# base-board.net
KiCad netlist of a schematic drawn in Altium Designer
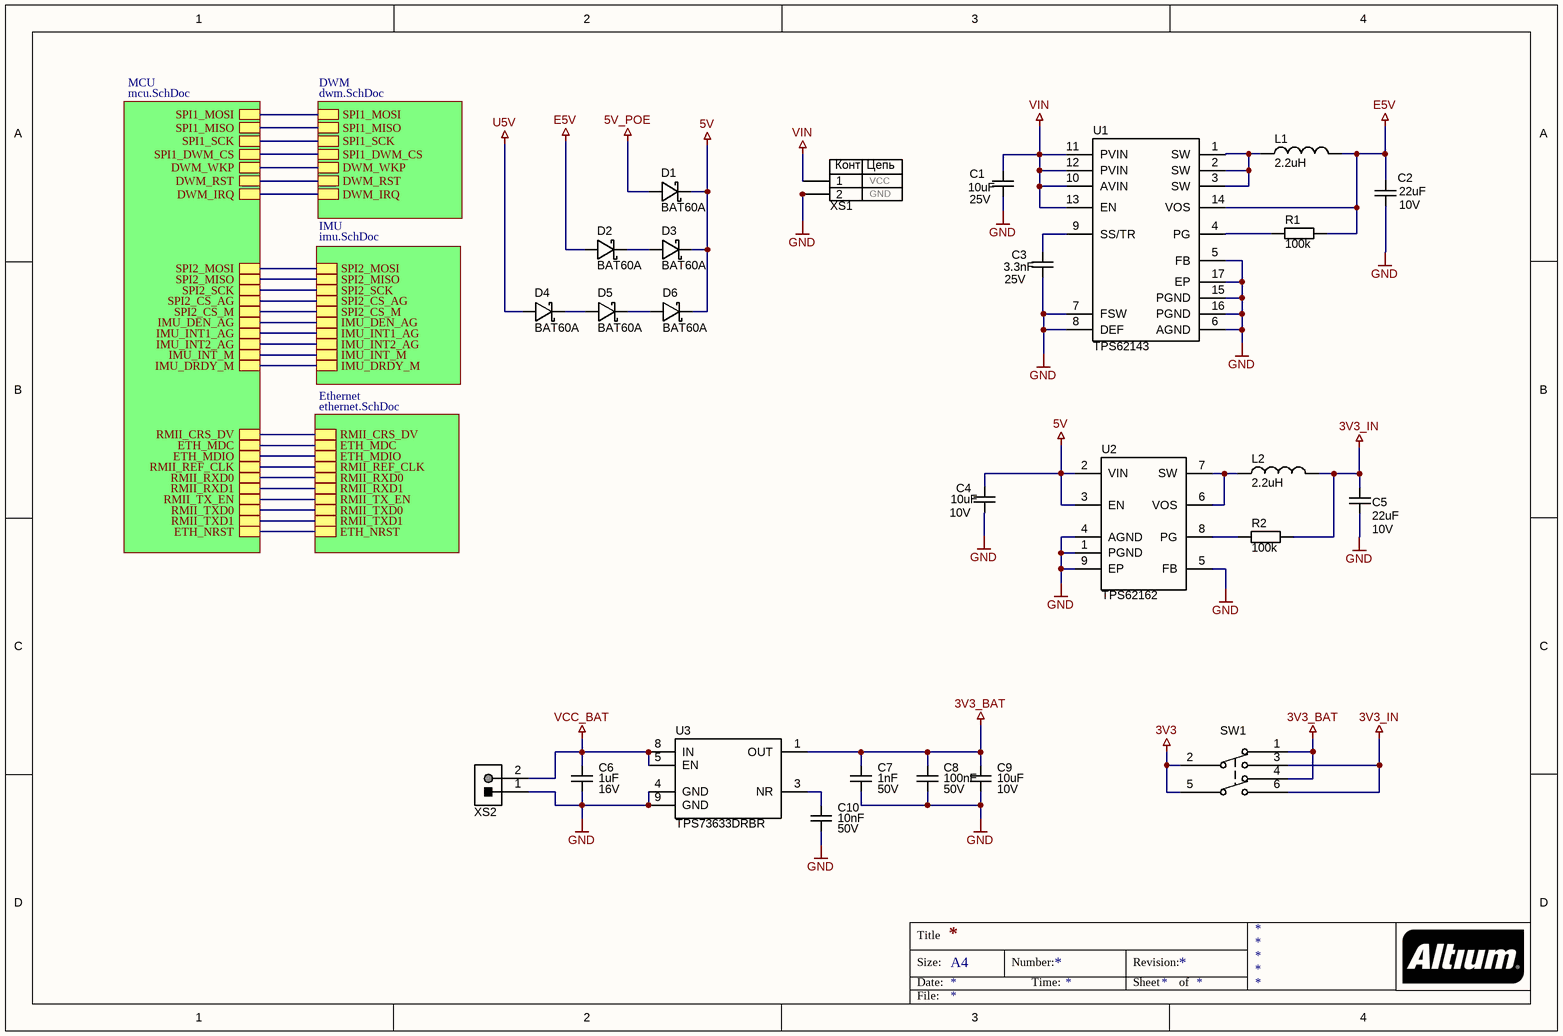
[diagram p0: base-board.SchDoc]

(export (version "E")
  (design (tool "Eeschema 10.0.6"))
  (components
    (comp (ref "C1")
      (value "10uF")
      (footprint "C1210")
      (fields (field (name "VOLTAGE") "25V") (field (name "Comment") "C1210"))
      (libsource (lib "DZ_LIB") (part "C1210"))
    )
    (comp (ref "C2")
      (value "22uF")
      (footprint "C1210")
      (fields (field (name "VOLTAGE") "10V") (field (name "Comment") "C1210"))
      (libsource (lib "DZ_LIB") (part "C1210"))
    )
    (comp (ref "C3")
      (value "3.3nF")
      (footprint "C0603")
      (fields (field (name "VOLTAGE") "25V") (field (name "Comment") "C0603"))
      (libsource (lib "DZ_LIB") (part "C0603"))
    )
    (comp (ref "C4")
      (value "10uF")
      (footprint "C0805")
      (fields (field (name "VOLTAGE") "10V") (field (name "Comment") "C0805"))
      (libsource (lib "DZ_LIB") (part "C0805"))
    )
    (comp (ref "C5")
      (value "22uF")
      (footprint "C0805")
      (fields (field (name "VOLTAGE") "10V") (field (name "Comment") "C0805"))
      (libsource (lib "DZ_LIB") (part "C0805"))
    )
    (comp (ref "C6")
      (value "1uF")
      (footprint "C0805")
      (fields (field (name "VOLTAGE") "16V") (field (name "Comment") "C0805"))
      (libsource (lib "DZ_LIB") (part "C0805"))
    )
    (comp (ref "C7")
      (value "1nF")
      (footprint "C0805")
      (fields (field (name "VOLTAGE") "50V") (field (name "Comment") "C0805"))
      (libsource (lib "DZ_LIB") (part "C0805"))
    )
    (comp (ref "C8")
      (value "100nF")
      (footprint "C0603")
      (fields (field (name "VOLTAGE") "50V") (field (name "Comment") "C0603"))
      (libsource (lib "DZ_LIB") (part "C0603"))
    )
    (comp (ref "C9")
      (value "10uF")
      (footprint "C0603")
      (fields (field (name "VOLTAGE") "10V") (field (name "Comment") "C0603"))
      (libsource (lib "DZ_LIB") (part "C0603"))
    )
    (comp (ref "C10")
      (value "10nF")
      (footprint "C0603")
      (fields (field (name "VOLTAGE") "50V") (field (name "Comment") "C0603"))
      (libsource (lib "DZ_LIB") (part "C0603"))
    )
    (comp (ref "D1")
      (value "BAT60A")
      (footprint "SOD-323-2")
      (description "Shottky Diode 10V 3A")
      (libsource (lib "DZ_LIB") (part "BAT60J"))
    )
    (comp (ref "D2")
      (value "BAT60A")
      (footprint "SOD-323-2")
      (description "Shottky Diode 10V 3A")
      (libsource (lib "DZ_LIB") (part "BAT60J"))
    )
    (comp (ref "D3")
      (value "BAT60A")
      (footprint "SOD-323-2")
      (description "Shottky Diode 10V 3A")
      (libsource (lib "DZ_LIB") (part "BAT60J"))
    )
    (comp (ref "D4")
      (value "BAT60A")
      (footprint "SOD-323-2")
      (description "Shottky Diode 10V 3A")
      (libsource (lib "DZ_LIB") (part "BAT60J"))
    )
    (comp (ref "D5")
      (value "BAT60A")
      (footprint "SOD-323-2")
      (description "Shottky Diode 10V 3A")
      (libsource (lib "DZ_LIB") (part "BAT60J"))
    )
    (comp (ref "D6")
      (value "BAT60A")
      (footprint "SOD-323-2")
      (description "Shottky Diode 10V 3A")
      (libsource (lib "DZ_LIB") (part "BAT60J"))
    )
    (comp (ref "L1")
      (value "2.2uH")
      (footprint "IND2220")
      (description "FIXED IND 2.2UH 2.5A 31 MOHM SMD")
      (fields (field (name "Comment") "LQH55PN2R2NR0"))
      (libsource (lib "DZ_LIB") (part "LQH55PN2R2NR0"))
    )
    (comp (ref "L2")
      (value "2.2uH")
      (footprint "IND2220")
      (description "FIXED IND 2.2UH 2.5A 31 MOHM SMD")
      (fields (field (name "Comment") "LQH55PN2R2NR0"))
      (libsource (lib "DZ_LIB") (part "LQH55PN2R2NR0"))
    )
    (comp (ref "R1")
      (value "100k")
      (footprint "SMD0603")
      (fields (field (name "Comment") "R0603"))
      (libsource (lib "DZ_LIB") (part "R0603"))
    )
    (comp (ref "R2")
      (value "100k")
      (footprint "SMD0603")
      (fields (field (name "Comment") "R0603"))
      (libsource (lib "DZ_LIB") (part "R0603"))
    )
    (comp (ref "SW1")
      (value "JS202011SCQN")
      (footprint "JS202011SCQN")
      (description "Switch Slide DPDT, 0.3 A, 6 V, -40 to 85 degC, 6-Pin SMD, RoHS, Tape and Reel")
      (fields (field (name "MANUFACTURER") "C&K Components"))
      (libsource (lib "DZ_LIB") (part "JS202011SCQN"))
    )
    (comp (ref "U1")
      (value "TPS62143")
      (footprint "QFN-16")
      (description "Buck 2A TI Fix 5V")
      (libsource (lib "DZ_LIB") (part "TPS62143RGT16"))
    )
    (comp (ref "U2")
      (value "TPS62162")
      (footprint "SON-8")
      (description "Buck 1A TI Fix 3.3V")
      (libsource (lib "DZ_LIB") (part "TPS62162DSG8"))
    )
    (comp (ref "U3")
      (value "TPS73633DRBR")
      (footprint "VSON-8")
      (description "IC REG LINEAR 3.3V 400MA 8SON")
      (libsource (lib "DZ_LIB") (part "TPS73633DRBR"))
    )
    (comp (ref "XS1")
      (value "PowerJack")
      (footprint "PowerJack")
      (libsource (lib "DZ_LIB") (part "PowerJack"))
    )
    (comp (ref "XS2")
      (value "S2B-PH-K-S")
      (footprint "S2B-PH-K-S")
      (fields (field (name "TOLERANCE") "20%"))
      (libsource (lib "DZ_LIB") (part "S2B-PH-K-S"))
    )
  )
  (nets
    (net (code "28") (name "3V3") (class "Default")
      (node (ref "SW1") (pin "2") (pinfunction "COM_2") (pintype "passive"))
      (node (ref "SW1") (pin "5") (pinfunction "COM_5") (pintype "passive"))
    )
    (net (code "29") (name "3V3_BAT") (class "Default")
      (node (ref "C7") (pin "2") (pinfunction "2_2") (pintype "passive"))
      (node (ref "C8") (pin "2") (pinfunction "2_2") (pintype "passive"))
      (node (ref "C9") (pin "2") (pinfunction "2_2") (pintype "passive"))
      (node (ref "SW1") (pin "1") (pinfunction "1_1") (pintype "passive"))
      (node (ref "SW1") (pin "4") (pinfunction "4_4") (pintype "passive"))
      (node (ref "U3") (pin "1") (pinfunction "OUT_1") (pintype "passive"))
    )
    (net (code "30") (name "3V3_IN") (class "Default")
      (node (ref "C5") (pin "2") (pinfunction "2_2") (pintype "passive"))
      (node (ref "L2") (pin "2") (pinfunction "2_2") (pintype "passive"))
      (node (ref "R2") (pin "2") (pinfunction "2_2") (pintype "passive"))
      (node (ref "SW1") (pin "3") (pinfunction "3_3") (pintype "passive"))
      (node (ref "SW1") (pin "6") (pinfunction "6_6") (pintype "passive"))
    )
    (net (code "31") (name "5V") (class "Default")
      (node (ref "C4") (pin "2") (pinfunction "2_2") (pintype "passive"))
      (node (ref "D1") (pin "2") (pinfunction "K_2") (pintype "passive"))
      (node (ref "D3") (pin "2") (pinfunction "K_2") (pintype "passive"))
      (node (ref "D6") (pin "2") (pinfunction "K_2") (pintype "passive"))
      (node (ref "U2") (pin "2") (pinfunction "VIN_2") (pintype "power_in"))
      (node (ref "U2") (pin "3") (pinfunction "EN_3") (pintype "passive"))
    )
    (net (code "32") (name "5V_POE") (class "Default")
      (node (ref "D1") (pin "1") (pinfunction "A_1") (pintype "passive"))
    )
    (net (code "33") (name "E5V") (class "Default")
      (node (ref "C2") (pin "2") (pinfunction "2_2") (pintype "passive"))
      (node (ref "D2") (pin "1") (pinfunction "A_1") (pintype "passive"))
      (node (ref "L1") (pin "2") (pinfunction "2_2") (pintype "passive"))
      (node (ref "R1") (pin "2") (pinfunction "2_2") (pintype "passive"))
      (node (ref "U1") (pin "14") (pinfunction "VOS_14") (pintype "passive"))
    )
    (net (code "34") (name "GND") (class "Default")
      (node (ref "C1") (pin "1") (pinfunction "1_1") (pintype "passive"))
      (node (ref "C10") (pin "1") (pinfunction "1_1") (pintype "passive"))
      (node (ref "C2") (pin "1") (pinfunction "1_1") (pintype "passive"))
      (node (ref "C3") (pin "1") (pinfunction "1_1") (pintype "passive"))
      (node (ref "C4") (pin "1") (pinfunction "1_1") (pintype "passive"))
      (node (ref "C5") (pin "1") (pinfunction "1_1") (pintype "passive"))
      (node (ref "C6") (pin "1") (pinfunction "1_1") (pintype "passive"))
      (node (ref "C7") (pin "1") (pinfunction "1_1") (pintype "passive"))
      (node (ref "C8") (pin "1") (pinfunction "1_1") (pintype "passive"))
      (node (ref "C9") (pin "1") (pinfunction "1_1") (pintype "passive"))
      (node (ref "U1") (pin "15") (pinfunction "PGND_15") (pintype "passive"))
      (node (ref "U1") (pin "16") (pinfunction "PGND_16") (pintype "passive"))
      (node (ref "U1") (pin "17") (pinfunction "EP_17") (pintype "passive"))
      (node (ref "U1") (pin "5") (pinfunction "FB_5") (pintype "passive"))
      (node (ref "U1") (pin "6") (pinfunction "AGND_6") (pintype "passive"))
      (node (ref "U1") (pin "7") (pinfunction "FSW_7") (pintype "passive"))
      (node (ref "U1") (pin "8") (pinfunction "DEF_8") (pintype "passive"))
      (node (ref "U2") (pin "1") (pinfunction "PGND_1") (pintype "power_in"))
      (node (ref "U2") (pin "4") (pinfunction "AGND_4") (pintype "power_in"))
      (node (ref "U2") (pin "5") (pinfunction "FB_5") (pintype "passive"))
      (node (ref "U2") (pin "9") (pinfunction "EP_9") (pintype "power_in"))
      (node (ref "U3") (pin "4") (pinfunction "GND_4") (pintype "passive"))
      (node (ref "U3") (pin "9") (pinfunction "GND_9") (pintype "passive"))
      (node (ref "XS1") (pin "2") (pinfunction "2_2") (pintype "passive"))
      (node (ref "XS1") (pin "3") (pinfunction "3_3") (pintype "passive"))
      (node (ref "XS2") (pin "1") (pinfunction "1_1") (pintype "passive"))
    )
    (net (code "35") (name "Net-(D2-K)") (class "Default")
      (node (ref "D2") (pin "2") (pinfunction "K_2") (pintype "passive"))
      (node (ref "D3") (pin "1") (pinfunction "A_1") (pintype "passive"))
    )
    (net (code "36") (name "Net-(D4-K)") (class "Default")
      (node (ref "D4") (pin "2") (pinfunction "K_2") (pintype "passive"))
      (node (ref "D5") (pin "1") (pinfunction "A_1") (pintype "passive"))
    )
    (net (code "37") (name "Net-(D5-K)") (class "Default")
      (node (ref "D5") (pin "2") (pinfunction "K_2") (pintype "passive"))
      (node (ref "D6") (pin "1") (pinfunction "A_1") (pintype "passive"))
    )
    (net (code "38") (name "Net-(L1-Pad1)") (class "Default")
      (node (ref "L1") (pin "1") (pinfunction "1_1") (pintype "passive"))
      (node (ref "U1") (pin "1") (pinfunction "SW_1") (pintype "passive"))
      (node (ref "U1") (pin "2") (pinfunction "SW_2") (pintype "passive"))
      (node (ref "U1") (pin "3") (pinfunction "SW_3") (pintype "passive"))
    )
    (net (code "39") (name "Net-(U1-PG)") (class "Default")
      (node (ref "R1") (pin "1") (pinfunction "1_1") (pintype "passive"))
      (node (ref "U1") (pin "4") (pinfunction "PG_4") (pintype "passive"))
    )
    (net (code "40") (name "Net-(U1-SS{slash}TR)") (class "Default")
      (node (ref "C3") (pin "2") (pinfunction "2_2") (pintype "passive"))
      (node (ref "U1") (pin "9") (pinfunction "SS/TR_9") (pintype "passive"))
    )
    (net (code "41") (name "Net-(U2-PG)") (class "Default")
      (node (ref "R2") (pin "1") (pinfunction "1_1") (pintype "passive"))
      (node (ref "U2") (pin "8") (pinfunction "PG_8") (pintype "tri_state"))
    )
    (net (code "42") (name "Net-(U2-SW)") (class "Default")
      (node (ref "L2") (pin "1") (pinfunction "1_1") (pintype "passive"))
      (node (ref "U2") (pin "6") (pinfunction "VOS_6") (pintype "passive"))
      (node (ref "U2") (pin "7") (pinfunction "SW_7") (pintype "power_in"))
    )
    (net (code "43") (name "Net-(U3-NR)") (class "Default")
      (node (ref "C10") (pin "2") (pinfunction "2_2") (pintype "passive"))
      (node (ref "U3") (pin "3") (pinfunction "NR_3") (pintype "passive"))
    )
    (net (code "44") (name "U5V") (class "Default")
      (node (ref "D4") (pin "1") (pinfunction "A_1") (pintype "passive"))
    )
    (net (code "45") (name "VCC_BAT") (class "Default")
      (node (ref "C6") (pin "2") (pinfunction "2_2") (pintype "passive"))
      (node (ref "U3") (pin "5") (pinfunction "EN_5") (pintype "passive"))
      (node (ref "U3") (pin "8") (pinfunction "IN_8") (pintype "passive"))
      (node (ref "XS2") (pin "2") (pinfunction "2_2") (pintype "passive"))
    )
    (net (code "46") (name "VIN") (class "Default")
      (node (ref "C1") (pin "2") (pinfunction "2_2") (pintype "passive"))
      (node (ref "U1") (pin "10") (pinfunction "AVIN_10") (pintype "passive"))
      (node (ref "U1") (pin "11") (pinfunction "PVIN_11") (pintype "passive"))
      (node (ref "U1") (pin "12") (pinfunction "PVIN_12") (pintype "passive"))
      (node (ref "U1") (pin "13") (pinfunction "EN_13") (pintype "passive"))
      (node (ref "XS1") (pin "1") (pinfunction "1_1") (pintype "passive"))
    )
  )
)
